# Nintendo_2DS_USB-C.net
KiCad netlist of a schematic drawn in EAGLE
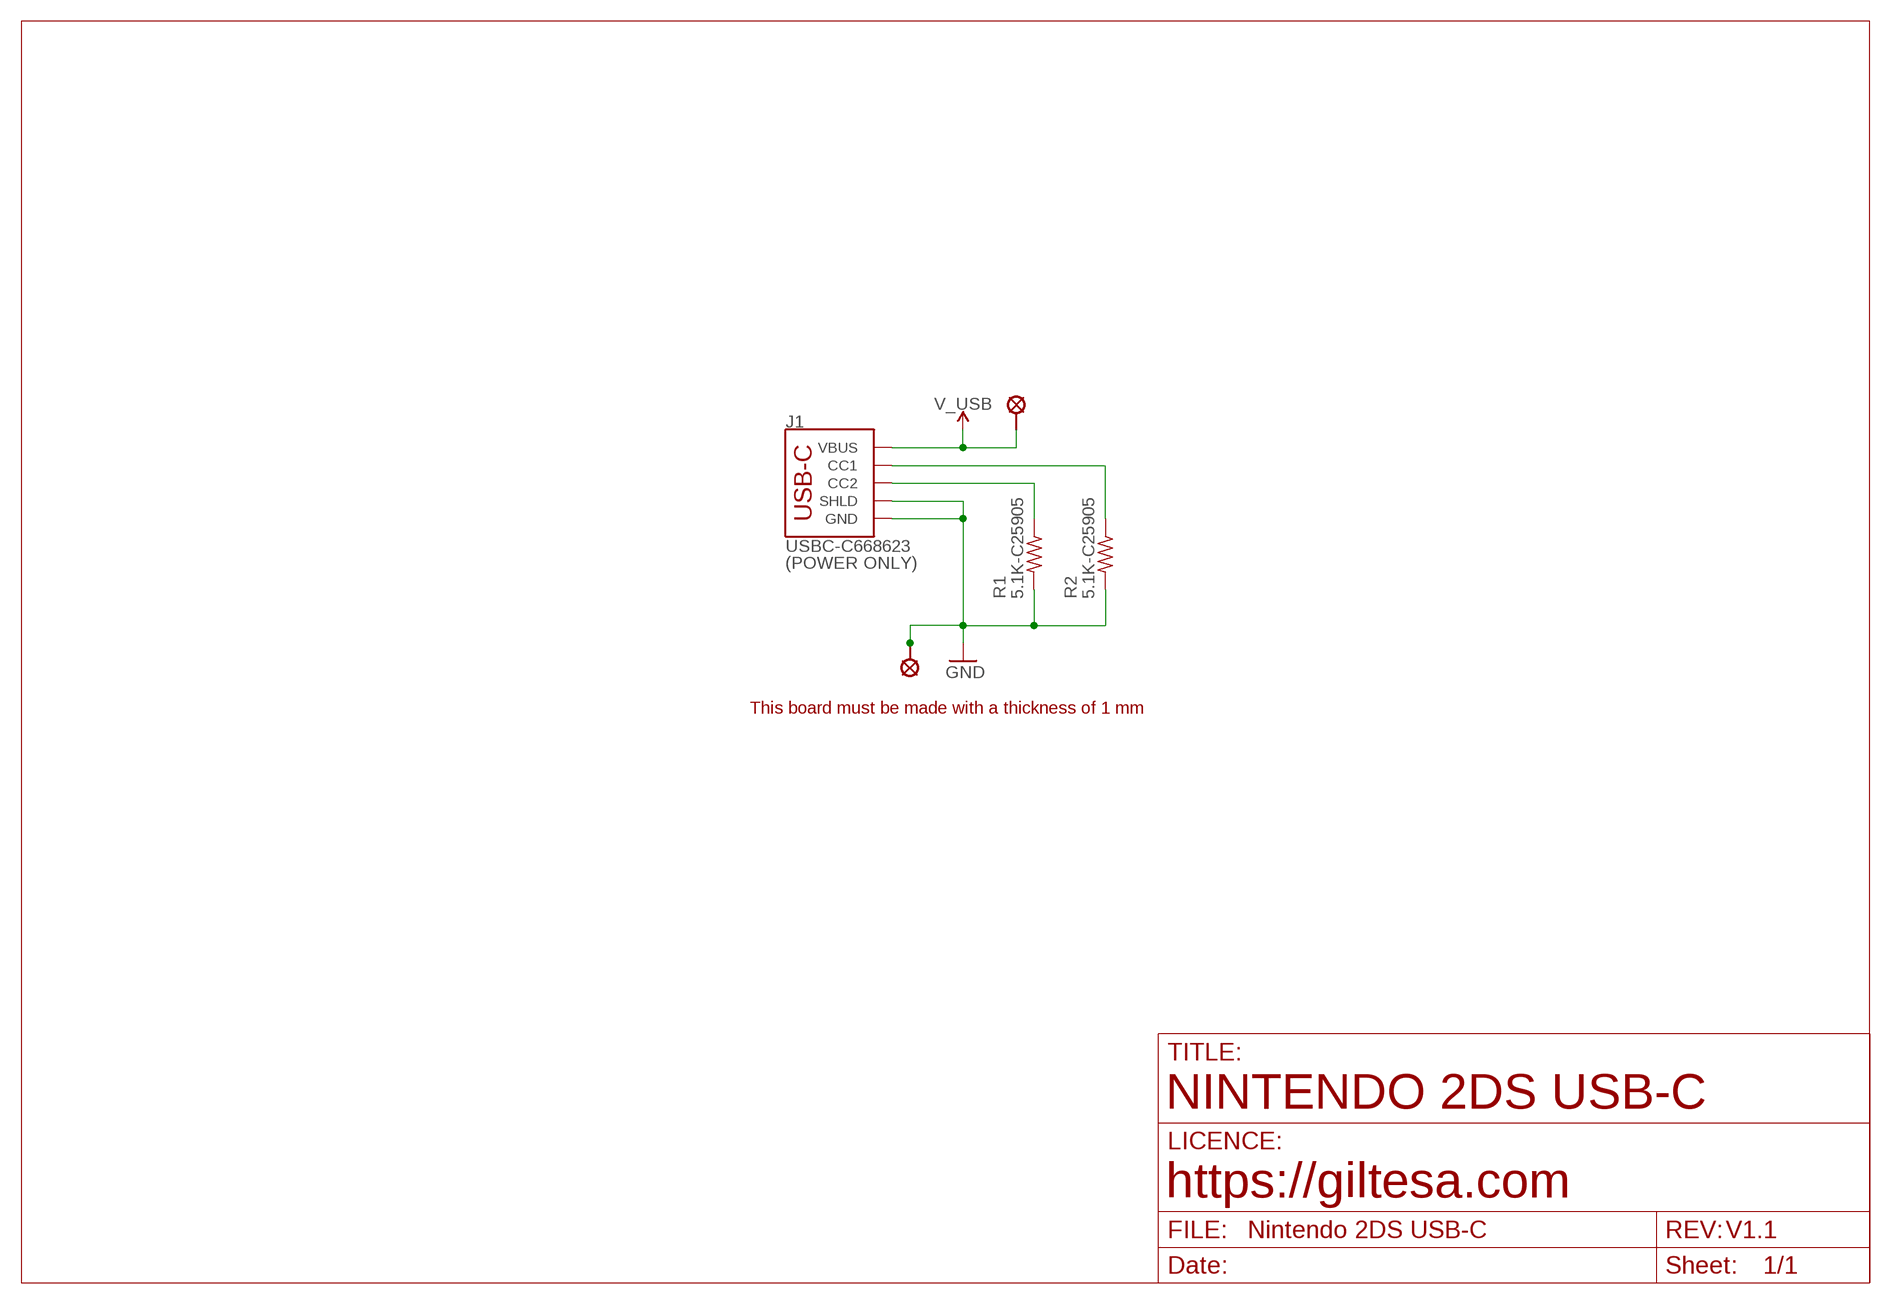
[diagram p0: schematic, sheet 1]

(export (version "E")
  (design (tool "Eeschema 10.0.6"))
  (components
    (comp (ref "J1")
      (value "USBC-C668623")
      (footprint "eagle-import:USB-C_6P")
      (libsource (lib "eagle-import") (part "USB-CPOWER"))
    )
    (comp (ref "R1")
      (value "5.1K-C25905")
      (footprint "eagle-import:R0402")
      (libsource (lib "eagle-import") (part "R0402"))
    )
    (comp (ref "R2")
      (value "5.1K-C25905")
      (footprint "eagle-import:R0402")
      (libsource (lib "eagle-import") (part "R0402"))
    )
    (comp (ref "U$2")
      (value "PAD_1.0H")
      (footprint "eagle-import:PAD_1.0_HALF_MASK")
      (libsource (lib "eagle-import") (part "PAD_1.0H"))
    )
    (comp (ref "U$3")
      (value "PAD_1.0H")
      (footprint "eagle-import:PAD_1.0_HALF_MASK")
      (libsource (lib "eagle-import") (part "PAD_1.0H"))
    )
    (comp (ref "U$4")
      (value "PAD_1.0H")
      (footprint "eagle-import:PAD_1.0_HALF_MASK")
      (libsource (lib "eagle-import") (part "PAD_1.0H"))
    )
    (comp (ref "U$5")
      (value "PAD_1.0H")
      (footprint "eagle-import:PAD_1.0_HALF_MASK")
      (libsource (lib "eagle-import") (part "PAD_1.0H"))
    )
  )
  (nets
    (net (code "1") (name "GND") (class "Default")
      (node (ref "J1") (pin "GND1") (pinfunction "GND_GND1") (pintype "bidirectional"))
      (node (ref "J1") (pin "GND2") (pinfunction "GND_GND2") (pintype "bidirectional"))
      (node (ref "J1") (pin "SHLD1") (pinfunction "SHLD_SHLD1") (pintype "bidirectional"))
      (node (ref "J1") (pin "SHLD2") (pinfunction "SHLD_SHLD2") (pintype "bidirectional"))
      (node (ref "J1") (pin "SHLD3") (pinfunction "SHLD_SHLD3") (pintype "bidirectional"))
      (node (ref "J1") (pin "SHLD4") (pinfunction "SHLD_SHLD4") (pintype "bidirectional"))
      (node (ref "J1") (pin "SHLD5") (pinfunction "SHLD_SHLD5") (pintype "bidirectional"))
      (node (ref "J1") (pin "SHLD6") (pinfunction "SHLD_SHLD6") (pintype "bidirectional"))
      (node (ref "J1") (pin "SHLD7") (pinfunction "SHLD_SHLD7") (pintype "bidirectional"))
      (node (ref "J1") (pin "SHLD8") (pinfunction "SHLD_SHLD8") (pintype "bidirectional"))
      (node (ref "R1") (pin "2") (pinfunction "2_2") (pintype "passive"))
      (node (ref "R2") (pin "2") (pinfunction "2_2") (pintype "passive"))
      (node (ref "U$3") (pin "P$1") (pinfunction "P$1_P$1") (pintype "bidirectional"))
      (node (ref "U$4") (pin "P$1") (pinfunction "P$1_P$1") (pintype "bidirectional"))
      (node (ref "U$5") (pin "P$1") (pinfunction "P$1_P$1") (pintype "bidirectional"))
    )
    (net (code "2") (name "Net-(J1-CC1)") (class "Default")
      (node (ref "J1") (pin "A5") (pinfunction "CC1_A5") (pintype "bidirectional"))
      (node (ref "R2") (pin "1") (pinfunction "1_1") (pintype "passive"))
    )
    (net (code "3") (name "Net-(J1-CC2)") (class "Default")
      (node (ref "J1") (pin "B5") (pinfunction "CC2_B5") (pintype "bidirectional"))
      (node (ref "R1") (pin "1") (pinfunction "1_1") (pintype "passive"))
    )
    (net (code "4") (name "V_USB") (class "Default")
      (node (ref "J1") (pin "VBUS1") (pinfunction "VBUS_VBUS1") (pintype "bidirectional"))
      (node (ref "J1") (pin "VBUS2") (pinfunction "VBUS_VBUS2") (pintype "bidirectional"))
      (node (ref "U$2") (pin "P$1") (pinfunction "P$1_P$1") (pintype "bidirectional"))
    )
  )
)
